# motor2_control.net
KiCad netlist of a schematic drawn in Altium Designer
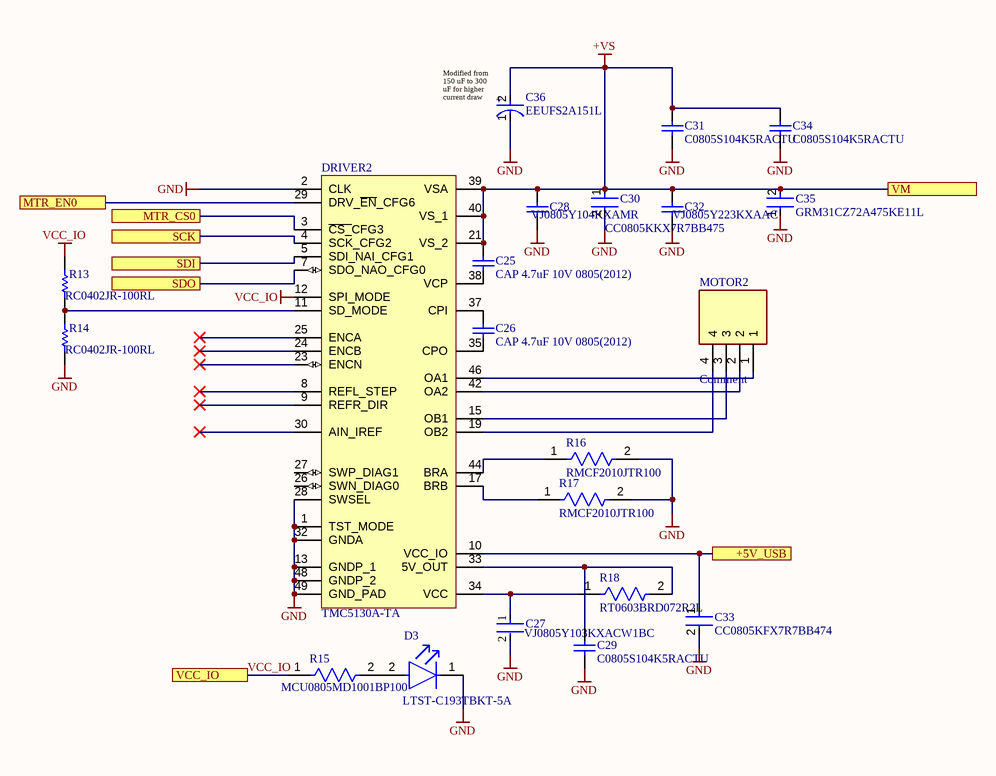
[diagram p0: motor2_control.SchDoc]

(export (version "E")
  (design (tool "Eeschema 10.0.6"))
  (components
    (comp (ref "C25")
      (value "CAP 4.7uF 10V 0805(2012)")
      (footprint "CAPC0805(2012)155_L")
      (description "CAP 4.7uF 10V ±10% 0805 (2012 Metric) Thickness 1.55mm SMD")
      (fields (field (name "TOLERANCE") "Â±10%"))
      (libsource (lib "Altium Content Vault") (part "CAP"))
    )
    (comp (ref "C26")
      (value "CAP 4.7uF 10V 0805(2012)")
      (footprint "CAPC0805(2012)155_L")
      (description "CAP 4.7uF 10V ±10% 0805 (2012 Metric) Thickness 1.55mm SMD")
      (fields (field (name "TOLERANCE") "Â±10%"))
      (libsource (lib "Altium Content Vault") (part "CAP"))
    )
    (comp (ref "C27")
      (value "VJ0805Y103KXACW1BC")
      (footprint "FP-VJ0805-MFG")
      (fields (field (name "TOLERANCE") "10%") (field (name "VOLTAGE") "50V"))
      (libsource (lib "Altium Content Vault") (part "b4654b650e69147ec39a6b967a45e02"))
    )
    (comp (ref "C28")
      (value "VJ0805Y104KXAMR")
      (footprint "CAPC2013X145X48NL20T23")
      (fields (field (name "MANUFACTURER") "Vitramon"))
      (libsource (lib "Altium Content Vault") (part "CAP"))
    )
    (comp (ref "C29")
      (value "C0805S104K5RACTU")
      (footprint "CAPC2013X145X50NL20T25")
      (fields (field (name "MANUFACTURER") "Kemet"))
      (libsource (lib "Altium Content Vault") (part "CAP"))
    )
    (comp (ref "C30")
      (value "CC0805KKX7R7BB475")
      (footprint "FP-CC0805-0_85-MFG")
      (description "CAP CER 4.7UF 16V X7R 0805")
      (fields
        (field (name "MANUFACTURER") "Yageo")
        (field (name "OCTOPART") "https://octopart.com/cc0805kkx7r7bb475-yageo-34429188")
      )
      (libsource (lib "Altium Content Vault") (part "11868f565c42a9108669ba33697ecf6"))
    )
    (comp (ref "C31")
      (value "C0805S104K5RACTU")
      (footprint "CAPC2013X145X50NL20T25")
      (fields (field (name "MANUFACTURER") "Kemet"))
      (libsource (lib "Altium Content Vault") (part "CAP"))
    )
    (comp (ref "C32")
      (value "VJ0805Y223KXAAC")
      (footprint "CAPC2013X145X48NL20T23")
      (fields (field (name "MANUFACTURER") "Vitramon"))
      (libsource (lib "Altium Content Vault") (part "CAP"))
    )
    (comp (ref "C33")
      (value "CC0805KFX7R7BB474")
      (footprint "FP-CC0805-0_85-MFG")
      (description "CC0805 470 nF X7R 10.00% 16 V")
      (fields
        (field (name "TOLERANCE") "0.1")
        (field (name "OCTOPART") "https://octopart.com/cc0805kfx7r7bb474-yageo-24732839")
      )
      (libsource (lib "Altium Content Vault") (part "11868f565c42a9108669ba33697ecf6"))
    )
    (comp (ref "C34")
      (value "C0805S104K5RACTU")
      (footprint "CAPC2013X145X50NL20T25")
      (fields (field (name "MANUFACTURER") "Kemet"))
      (libsource (lib "Altium Content Vault") (part "CAP"))
    )
    (comp (ref "C35")
      (value "GRM31CZ72A475KE11L")
      (footprint "FP-GRM31C-0_3-e0_3_0_9-MFG")
      (description "Chip Multilayer Ceramic Capacitors for General Purpose, 1206, 4.7uF, X7R, 15%, 10%, 100V")
      (libsource (lib "Altium Content Vault") (part "f23184f103b6ebe33a8c269c53dcba6"))
    )
    (comp (ref "C36")
      (value "EEUFS2A151L")
      (footprint "FP-RAD-TH-D_10_0_5-L_25_2-MFG")
      (description "Aluminum Electrolytic Capacitors (Radial Lead Type) 150uF ±20% 100V")
      (libsource (lib "Altium Content Vault") (part "a00bbbee19879c290e62620ae7e47b1"))
    )
    (comp (ref "D3")
      (value "LTST-C193TBKT-5A")
      (footprint "FP-LTST-C193TBKT-5A-MFG")
      (description "LED BLUE CLEAR CHIP SMD")
      (libsource (lib "Altium Content Vault") (part "8706943c75ba83719d021d2fdc84c58"))
    )
    (comp (ref "DRIVER2")
      (value "TMC5130A-TA")
      (footprint "TMC5130_TQFP48-EP_0.5_7.0X7.0")
      (fields (field (name "MANUFACTURER") "TRINAMIC"))
      (libsource (lib "TMC5130A-TA") (part "TMC5130A-TA"))
    )
    (comp (ref "MOTOR2")
      (value "Comment")
      (footprint "TE_282834-4")
      (fields (field (name "MF") "TE Connectivity") (field (name "MP") "282834-4"))
      (libsource (lib "282834-4") (part "282834-4"))
    )
    (comp (ref "R13")
      (value "RC0402JR-100RL")
      (footprint "RESC1005X40X25NL05T10")
      (fields (field (name "MANUFACTURER") "Yageo"))
      (libsource (lib "Altium Content Vault") (part "RES"))
    )
    (comp (ref "R14")
      (value "RC0402JR-100RL")
      (footprint "RESC1005X40X25NL05T10")
      (fields (field (name "MANUFACTURER") "Yageo"))
      (libsource (lib "Altium Content Vault") (part "RES"))
    )
    (comp (ref "R15")
      (value "MCU0805MD1001BP100")
      (footprint "FP-MCU0805-IPC_A")
      (description "RES 1.05K OHM 0.5% 1/5W 0805")
      (fields (field (name "TOLERANCE") "0.1%"))
      (libsource (lib "Altium Content Vault") (part "1029c3af85768c4190bb7ad29bc67b5"))
    )
    (comp (ref "R16")
      (value "RMCF2010JTR100")
      (footprint "FP-RMCF2010-IPC_B")
      (description "0.1Ω ±5% 0.75W 2010 Thick Film Chip Resistor AEC-Q200 compliant")
      (fields (field (name "TOLERANCE") "5%"))
      (libsource (lib "Altium Content Vault") (part "1029c3af85768c4190bb7ad29bc67b5"))
    )
    (comp (ref "R17")
      (value "RMCF2010JTR100")
      (footprint "FP-RMCF2010-IPC_B")
      (description "0.1Ω ±5% 0.75W 2010 Thick Film Chip Resistor AEC-Q200 compliant")
      (fields (field (name "TOLERANCE") "5%"))
      (libsource (lib "Altium Content Vault") (part "1029c3af85768c4190bb7ad29bc67b5"))
    )
    (comp (ref "R18")
      (value "RT0603BRD072R2L")
      (footprint "FP-RT0603-MFG")
      (description "RT0603 2.2Ω 0.1W 25 ppm/°C 0.10%")
      (fields
        (field (name "OCTOPART") "https://octopart.com/rt0603brd072r2l-yageo-80827805")
        (field (name "TOLERANCE") "0.001")
      )
      (libsource (lib "Altium Content Vault") (part "1029c3af85768c4190bb7ad29bc67b5"))
    )
  )
  (nets
    (net (code "1") (name "+VS") (class "Default")
      (node (ref "C25") (pin "2") (pinfunction "2_2") (pintype "passive"))
      (node (ref "C28") (pin "2") (pinfunction "2_2") (pintype "passive"))
      (node (ref "C30") (pin "1") (pinfunction "1_1") (pintype "passive"))
      (node (ref "C31") (pin "2") (pinfunction "2_2") (pintype "passive"))
      (node (ref "C32") (pin "2") (pinfunction "2_2") (pintype "passive"))
      (node (ref "C34") (pin "2") (pinfunction "2_2") (pintype "passive"))
      (node (ref "C35") (pin "2") (pinfunction "2_2") (pintype "passive"))
      (node (ref "C36") (pin "2") (pinfunction "A_2") (pintype "passive"))
      (node (ref "DRIVER2") (pin "21") (pinfunction "VS_2_21") (pintype "power_in"))
      (node (ref "DRIVER2") (pin "39") (pinfunction "VSA_39") (pintype "power_in"))
      (node (ref "DRIVER2") (pin "40") (pinfunction "VS_1_40") (pintype "power_in"))
    )
    (net (code "2") (name "/+5V_USB") (class "Default")
      (node (ref "C33") (pin "1") (pinfunction "1_1") (pintype "passive"))
      (node (ref "DRIVER2") (pin "10") (pinfunction "VCC_IO_10") (pintype "power_in"))
    )
    (net (code "3") (name "/MTR_CS0") (class "Default")
      (node (ref "DRIVER2") (pin "3") (pinfunction "~{CS_}CFG3_3") (pintype "passive"))
    )
    (net (code "4") (name "/MTR_EN0") (class "Default")
      (node (ref "DRIVER2") (pin "29") (pinfunction "DRV_~{EN}_CFG6_29") (pintype "passive"))
    )
    (net (code "5") (name "/SCK") (class "Default")
      (node (ref "DRIVER2") (pin "4") (pinfunction "SCK_CFG2_4") (pintype "passive"))
    )
    (net (code "6") (name "/SDI") (class "Default")
      (node (ref "DRIVER2") (pin "5") (pinfunction "SDI_NAI_CFG1_5") (pintype "passive"))
    )
    (net (code "7") (name "/SDO") (class "Default")
      (node (ref "DRIVER2") (pin "7") (pinfunction "SDO_NAO_CFG0_7") (pintype "bidirectional"))
    )
    (net (code "8") (name "GND") (class "Default")
      (node (ref "C27") (pin "2") (pinfunction "2_2") (pintype "passive"))
      (node (ref "C28") (pin "1") (pinfunction "1_1") (pintype "passive"))
      (node (ref "C29") (pin "1") (pinfunction "1_1") (pintype "passive"))
      (node (ref "C30") (pin "2") (pinfunction "2_2") (pintype "passive"))
      (node (ref "C31") (pin "1") (pinfunction "1_1") (pintype "passive"))
      (node (ref "C32") (pin "1") (pinfunction "1_1") (pintype "passive"))
      (node (ref "C33") (pin "2") (pinfunction "2_2") (pintype "passive"))
      (node (ref "C34") (pin "1") (pinfunction "1_1") (pintype "passive"))
      (node (ref "C35") (pin "1") (pinfunction "1_1") (pintype "passive"))
      (node (ref "C36") (pin "1") (pinfunction "C_1") (pintype "passive"))
      (node (ref "D3") (pin "1") (pinfunction "C_1") (pintype "passive"))
      (node (ref "DRIVER2") (pin "1") (pinfunction "TST_MODE_1") (pintype "passive"))
      (node (ref "DRIVER2") (pin "13") (pinfunction "GNDP_1_13") (pintype "passive"))
      (node (ref "DRIVER2") (pin "2") (pinfunction "CLK_2") (pintype "passive"))
      (node (ref "DRIVER2") (pin "28") (pinfunction "SWSEL_28") (pintype "passive"))
      (node (ref "DRIVER2") (pin "32") (pinfunction "GNDA_32") (pintype "passive"))
      (node (ref "DRIVER2") (pin "48") (pinfunction "GNDP_2_48") (pintype "passive"))
      (node (ref "DRIVER2") (pin "49") (pinfunction "GND_PAD_49") (pintype "passive"))
      (node (ref "R14") (pin "2") (pinfunction "2_2") (pintype "passive"))
      (node (ref "R16") (pin "2") (pinfunction "2_2") (pintype "passive"))
      (node (ref "R17") (pin "2") (pinfunction "2_2") (pintype "passive"))
    )
    (net (code "9") (name "Net-(D3-A)") (class "Default")
      (node (ref "D3") (pin "2") (pinfunction "A_2") (pintype "passive"))
      (node (ref "R15") (pin "2") (pinfunction "2_2") (pintype "passive"))
    )
    (net (code "10") (name "Net-(DRIVER2-5V_OUT)") (class "Default")
      (node (ref "C29") (pin "2") (pinfunction "2_2") (pintype "passive"))
      (node (ref "DRIVER2") (pin "33") (pinfunction "5V_OUT_33") (pintype "power_in"))
      (node (ref "R18") (pin "2") (pinfunction "2_2") (pintype "passive"))
    )
    (net (code "11") (name "Net-(DRIVER2-BRA)") (class "Default")
      (node (ref "DRIVER2") (pin "44") (pinfunction "BRA_44") (pintype "passive"))
      (node (ref "R16") (pin "1") (pinfunction "1_1") (pintype "passive"))
    )
    (net (code "12") (name "Net-(DRIVER2-BRB)") (class "Default")
      (node (ref "DRIVER2") (pin "17") (pinfunction "BRB_17") (pintype "passive"))
      (node (ref "R17") (pin "1") (pinfunction "1_1") (pintype "passive"))
    )
    (net (code "13") (name "Net-(DRIVER2-CPI)") (class "Default")
      (node (ref "C26") (pin "2") (pinfunction "2_2") (pintype "passive"))
      (node (ref "DRIVER2") (pin "37") (pinfunction "CPI_37") (pintype "passive"))
    )
    (net (code "14") (name "Net-(DRIVER2-CPO)") (class "Default")
      (node (ref "C26") (pin "1") (pinfunction "1_1") (pintype "passive"))
      (node (ref "DRIVER2") (pin "35") (pinfunction "CPO_35") (pintype "passive"))
    )
    (net (code "15") (name "Net-(DRIVER2-OA1)") (class "Default")
      (node (ref "DRIVER2") (pin "46") (pinfunction "OA1_46") (pintype "passive"))
      (node (ref "MOTOR2") (pin "1") (pinfunction "1_1") (pintype "passive"))
    )
    (net (code "16") (name "Net-(DRIVER2-OA2)") (class "Default")
      (node (ref "DRIVER2") (pin "42") (pinfunction "OA2_42") (pintype "passive"))
      (node (ref "MOTOR2") (pin "2") (pinfunction "2_2") (pintype "passive"))
    )
    (net (code "17") (name "Net-(DRIVER2-OB1)") (class "Default")
      (node (ref "DRIVER2") (pin "15") (pinfunction "OB1_15") (pintype "passive"))
      (node (ref "MOTOR2") (pin "3") (pinfunction "3_3") (pintype "passive"))
    )
    (net (code "18") (name "Net-(DRIVER2-OB2)") (class "Default")
      (node (ref "DRIVER2") (pin "19") (pinfunction "OB2_19") (pintype "passive"))
      (node (ref "MOTOR2") (pin "4") (pinfunction "4_4") (pintype "passive"))
    )
    (net (code "19") (name "Net-(DRIVER2-SD_MODE)") (class "Default")
      (node (ref "DRIVER2") (pin "11") (pinfunction "SD_MODE_11") (pintype "passive"))
      (node (ref "R13") (pin "2") (pinfunction "2_2") (pintype "passive"))
      (node (ref "R14") (pin "1") (pinfunction "1_1") (pintype "passive"))
    )
    (net (code "20") (name "Net-(DRIVER2-VCC)") (class "Default")
      (node (ref "C27") (pin "1") (pinfunction "1_1") (pintype "passive"))
      (node (ref "DRIVER2") (pin "34") (pinfunction "VCC_34") (pintype "power_in"))
      (node (ref "R18") (pin "1") (pinfunction "1_1") (pintype "passive"))
    )
    (net (code "21") (name "Net-(DRIVER2-VCP)") (class "Default")
      (node (ref "C25") (pin "1") (pinfunction "1_1") (pintype "passive"))
      (node (ref "DRIVER2") (pin "38") (pinfunction "VCP_38") (pintype "power_in"))
    )
    (net (code "22") (name "VCC_IO") (class "Default")
      (node (ref "DRIVER2") (pin "12") (pinfunction "SPI_MODE_12") (pintype "passive"))
      (node (ref "R13") (pin "1") (pinfunction "1_1") (pintype "passive"))
      (node (ref "R15") (pin "1") (pinfunction "1_1") (pintype "passive"))
    )
    (net (code "23") (name "unconnected-(DRIVER2-AIN_IREF-Pad30)") (class "Default")
      (node (ref "DRIVER2") (pin "30") (pinfunction "AIN_IREF_30") (pintype "passive+no_connect"))
    )
    (net (code "24") (name "unconnected-(DRIVER2-ENCA-Pad25)") (class "Default")
      (node (ref "DRIVER2") (pin "25") (pinfunction "ENCA_25") (pintype "passive+no_connect"))
    )
    (net (code "25") (name "unconnected-(DRIVER2-ENCB-Pad24)") (class "Default")
      (node (ref "DRIVER2") (pin "24") (pinfunction "ENCB_24") (pintype "passive+no_connect"))
    )
    (net (code "26") (name "unconnected-(DRIVER2-ENCN-Pad23)") (class "Default")
      (node (ref "DRIVER2") (pin "23") (pinfunction "ENCN_23") (pintype "bidirectional+no_connect"))
    )
    (net (code "27") (name "unconnected-(DRIVER2-REFL_STEP-Pad8)") (class "Default")
      (node (ref "DRIVER2") (pin "8") (pinfunction "REFL_STEP_8") (pintype "passive+no_connect"))
    )
    (net (code "28") (name "unconnected-(DRIVER2-REFR_DIR-Pad9)") (class "Default")
      (node (ref "DRIVER2") (pin "9") (pinfunction "REFR_DIR_9") (pintype "passive+no_connect"))
    )
    (net (code "29") (name "unconnected-(DRIVER2-SWN_DIAG0-Pad26)") (class "Default")
      (node (ref "DRIVER2") (pin "26") (pinfunction "SWN_DIAG0_26") (pintype "bidirectional"))
    )
    (net (code "30") (name "unconnected-(DRIVER2-SWP_DIAG1-Pad27)") (class "Default")
      (node (ref "DRIVER2") (pin "27") (pinfunction "SWP_DIAG1_27") (pintype "bidirectional"))
    )
  )
)
